# FXLoader_rev_A.net
KiCad netlist of a schematic drawn in EAGLE
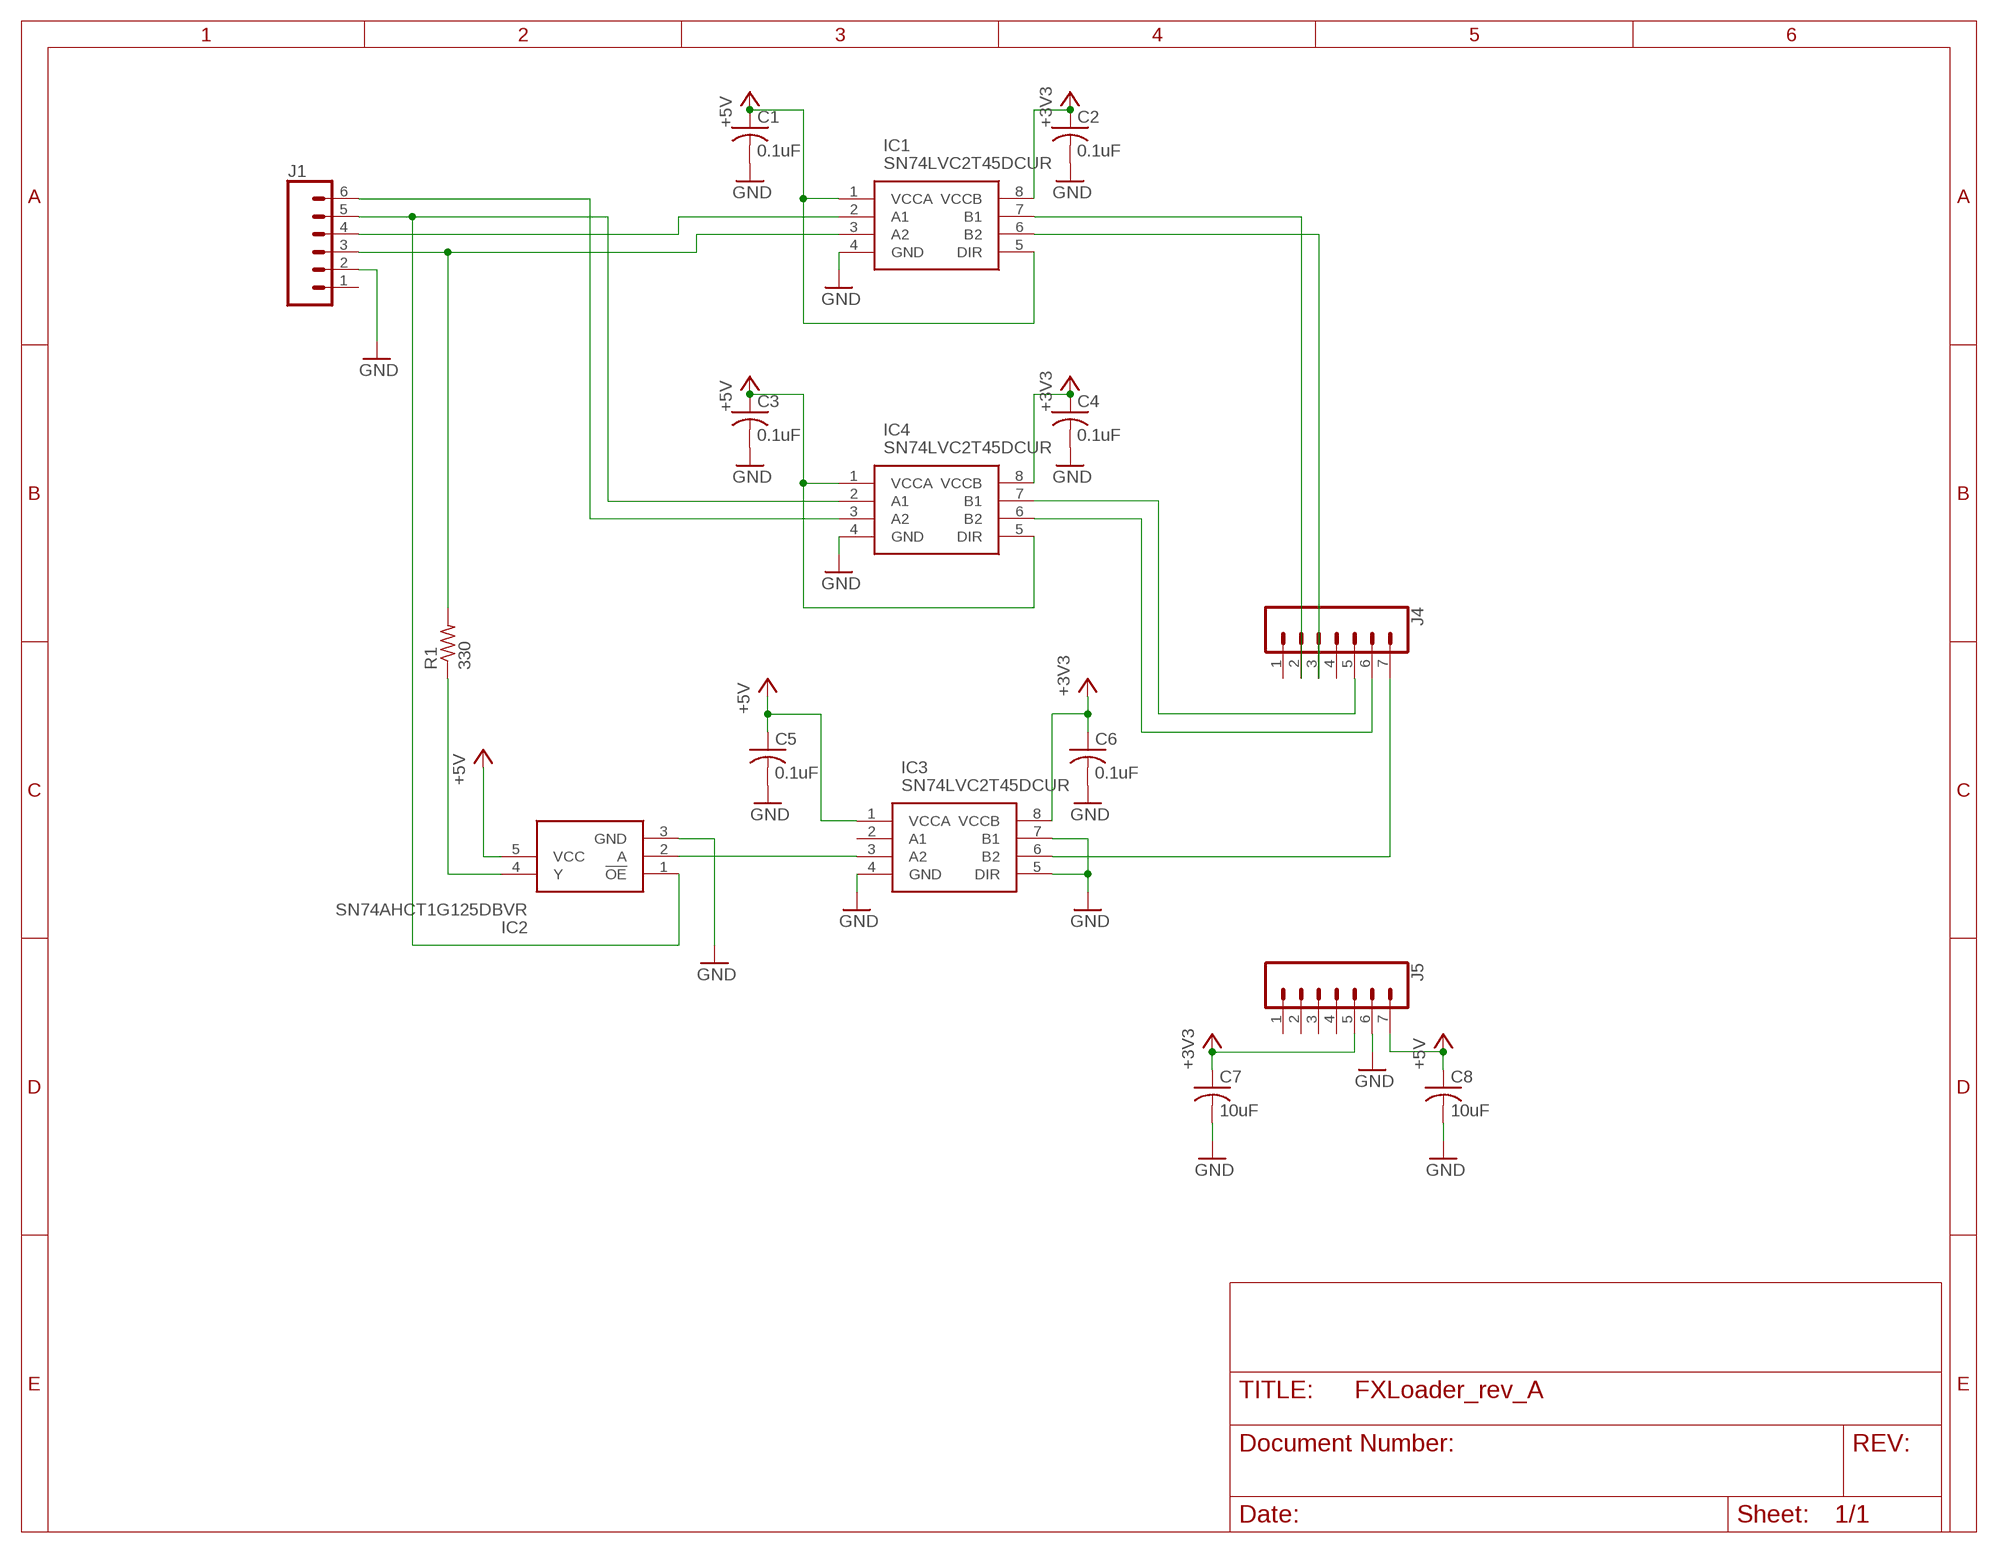
[diagram p0: schematic, sheet 1]

(export (version "E")
  (design (tool "Eeschema 10.0.6"))
  (components
    (comp (ref "C1")
      (value "0.1uF")
      (footprint "eagle-import:C0402")
      (libsource (lib "eagle-import") (part "C-USC0402"))
    )
    (comp (ref "C2")
      (value "0.1uF")
      (footprint "eagle-import:C0402")
      (libsource (lib "eagle-import") (part "C-USC0402"))
    )
    (comp (ref "C3")
      (value "0.1uF")
      (footprint "eagle-import:C0402")
      (libsource (lib "eagle-import") (part "C-USC0402"))
    )
    (comp (ref "C4")
      (value "0.1uF")
      (footprint "eagle-import:C0402")
      (libsource (lib "eagle-import") (part "C-USC0402"))
    )
    (comp (ref "C5")
      (value "0.1uF")
      (footprint "eagle-import:C0402")
      (libsource (lib "eagle-import") (part "C-USC0402"))
    )
    (comp (ref "C6")
      (value "0.1uF")
      (footprint "eagle-import:C0402")
      (libsource (lib "eagle-import") (part "C-USC0402"))
    )
    (comp (ref "C7")
      (value "10uF")
      (footprint "eagle-import:C0805")
      (libsource (lib "eagle-import") (part "C-USC0805"))
    )
    (comp (ref "C8")
      (value "10uF")
      (footprint "eagle-import:C0805")
      (libsource (lib "eagle-import") (part "C-USC0805"))
    )
    (comp (ref "IC1")
      (value "SN74LVC2T45DCUR")
      (footprint "eagle-import:SOP50P310X90-8N")
      (fields (field (name "MOUSER_PART_NUMBER") "595-SN74LVC2T45DCUR"))
      (libsource (lib "eagle-import") (part "SN74LVC2T45DCUR"))
    )
    (comp (ref "IC2")
      (value "SN74AHCT1G125DBVR")
      (footprint "eagle-import:SOT95P280X145-5N")
      (fields (field (name "MOUSER_PART_NUMBER") "595-SNAHCT1G125DBVR"))
      (libsource (lib "eagle-import") (part "SN74AHCT1G125DBVR"))
    )
    (comp (ref "IC3")
      (value "SN74LVC2T45DCUR")
      (footprint "eagle-import:SOP50P310X90-8N")
      (fields (field (name "MOUSER_PART_NUMBER") "595-SN74LVC2T45DCUR"))
      (libsource (lib "eagle-import") (part "SN74LVC2T45DCUR"))
    )
    (comp (ref "IC4")
      (value "SN74LVC2T45DCUR")
      (footprint "eagle-import:SOP50P310X90-8N")
      (fields (field (name "MOUSER_PART_NUMBER") "595-SN74LVC2T45DCUR"))
      (libsource (lib "eagle-import") (part "SN74LVC2T45DCUR"))
    )
    (comp (ref "J1")
      (value "CONN_06NO_SILK_FEMALE_PTH")
      (footprint "eagle-import:1X06_NO_SILK")
      (libsource (lib "eagle-import") (part "CONN_06NO_SILK_FEMALE_PTH"))
    )
    (comp (ref "J4")
      (value "CONN_071X07_LONGPADS_OFFSET_B")
      (footprint "eagle-import:1X07_LONGPADS_OFFSET_B")
      (libsource (lib "eagle-import") (part "CONN_071X07_LONGPADS_OFFSET_B"))
    )
    (comp (ref "J5")
      (value "CONN_071X07_LONGPADS_OFFSET")
      (footprint "eagle-import:1X07_LONGPADS_OFFSET")
      (libsource (lib "eagle-import") (part "CONN_071X07_LONGPADS_OFFSET"))
    )
    (comp (ref "R1")
      (value "330")
      (footprint "eagle-import:R0402")
      (libsource (lib "eagle-import") (part "R-US_R0402"))
    )
  )
  (nets
    (net (code "1") (name "+3V3") (class "Default")
      (node (ref "C2") (pin "1") (pinfunction "1_1") (pintype "passive"))
      (node (ref "C4") (pin "1") (pinfunction "1_1") (pintype "passive"))
      (node (ref "C6") (pin "1") (pinfunction "1_1") (pintype "passive"))
      (node (ref "C7") (pin "1") (pinfunction "1_1") (pintype "passive"))
      (node (ref "IC1") (pin "8") (pinfunction "VCCB_8") (pintype "bidirectional"))
      (node (ref "IC3") (pin "8") (pinfunction "VCCB_8") (pintype "bidirectional"))
      (node (ref "IC4") (pin "8") (pinfunction "VCCB_8") (pintype "bidirectional"))
      (node (ref "J5") (pin "5") (pinfunction "5_5") (pintype "passive"))
    )
    (net (code "2") (name "+5V") (class "Default")
      (node (ref "C1") (pin "1") (pinfunction "1_1") (pintype "passive"))
      (node (ref "C3") (pin "1") (pinfunction "1_1") (pintype "passive"))
      (node (ref "C5") (pin "1") (pinfunction "1_1") (pintype "passive"))
      (node (ref "C8") (pin "1") (pinfunction "1_1") (pintype "passive"))
      (node (ref "IC1") (pin "1") (pinfunction "VCCA_1") (pintype "bidirectional"))
      (node (ref "IC1") (pin "5") (pinfunction "DIR_5") (pintype "bidirectional"))
      (node (ref "IC2") (pin "5") (pinfunction "VCC_5") (pintype "power_in"))
      (node (ref "IC3") (pin "1") (pinfunction "VCCA_1") (pintype "bidirectional"))
      (node (ref "IC4") (pin "1") (pinfunction "VCCA_1") (pintype "bidirectional"))
      (node (ref "IC4") (pin "5") (pinfunction "DIR_5") (pintype "bidirectional"))
      (node (ref "J5") (pin "7") (pinfunction "7_7") (pintype "passive"))
    )
    (net (code "3") (name "GND") (class "Default")
      (node (ref "C1") (pin "2") (pinfunction "2_2") (pintype "passive"))
      (node (ref "C2") (pin "2") (pinfunction "2_2") (pintype "passive"))
      (node (ref "C3") (pin "2") (pinfunction "2_2") (pintype "passive"))
      (node (ref "C4") (pin "2") (pinfunction "2_2") (pintype "passive"))
      (node (ref "C5") (pin "2") (pinfunction "2_2") (pintype "passive"))
      (node (ref "C6") (pin "2") (pinfunction "2_2") (pintype "passive"))
      (node (ref "C7") (pin "2") (pinfunction "2_2") (pintype "passive"))
      (node (ref "C8") (pin "2") (pinfunction "2_2") (pintype "passive"))
      (node (ref "IC1") (pin "4") (pinfunction "GND_4") (pintype "bidirectional"))
      (node (ref "IC2") (pin "3") (pinfunction "GND_3") (pintype "power_in"))
      (node (ref "IC3") (pin "4") (pinfunction "GND_4") (pintype "bidirectional"))
      (node (ref "IC3") (pin "5") (pinfunction "DIR_5") (pintype "bidirectional"))
      (node (ref "IC3") (pin "7") (pinfunction "B1_7") (pintype "bidirectional"))
      (node (ref "IC4") (pin "4") (pinfunction "GND_4") (pintype "bidirectional"))
      (node (ref "J1") (pin "2") (pinfunction "2_2") (pintype "passive"))
      (node (ref "J5") (pin "6") (pinfunction "6_6") (pintype "passive"))
    )
    (net (code "4") (name "Net-(IC1-A1)") (class "Default")
      (node (ref "IC1") (pin "2") (pinfunction "A1_2") (pintype "bidirectional"))
      (node (ref "J1") (pin "4") (pinfunction "4_4") (pintype "passive"))
    )
    (net (code "5") (name "Net-(IC1-A2)") (class "Default")
      (node (ref "IC1") (pin "3") (pinfunction "A2_3") (pintype "bidirectional"))
      (node (ref "J1") (pin "3") (pinfunction "3_3") (pintype "passive"))
      (node (ref "R1") (pin "2") (pinfunction "2_2") (pintype "passive"))
    )
    (net (code "6") (name "Net-(IC1-B1)") (class "Default")
      (node (ref "IC1") (pin "7") (pinfunction "B1_7") (pintype "bidirectional"))
      (node (ref "J4") (pin "2") (pinfunction "2_2") (pintype "passive"))
    )
    (net (code "7") (name "Net-(IC1-B2)") (class "Default")
      (node (ref "IC1") (pin "6") (pinfunction "B2_6") (pintype "bidirectional"))
      (node (ref "J4") (pin "3") (pinfunction "3_3") (pintype "passive"))
    )
    (net (code "8") (name "Net-(IC2-A)") (class "Default")
      (node (ref "IC2") (pin "2") (pinfunction "A_2") (pintype "bidirectional"))
      (node (ref "IC3") (pin "3") (pinfunction "A2_3") (pintype "bidirectional"))
    )
    (net (code "9") (name "Net-(IC2-Y)") (class "Default")
      (node (ref "IC2") (pin "4") (pinfunction "Y_4") (pintype "bidirectional"))
      (node (ref "R1") (pin "1") (pinfunction "1_1") (pintype "passive"))
    )
    (net (code "10") (name "Net-(IC2-~{OE})") (class "Default")
      (node (ref "IC2") (pin "1") (pinfunction "~{OE}_1") (pintype "bidirectional"))
      (node (ref "IC4") (pin "2") (pinfunction "A1_2") (pintype "bidirectional"))
      (node (ref "J1") (pin "5") (pinfunction "5_5") (pintype "passive"))
    )
    (net (code "11") (name "Net-(IC3-B2)") (class "Default")
      (node (ref "IC3") (pin "6") (pinfunction "B2_6") (pintype "bidirectional"))
      (node (ref "J4") (pin "7") (pinfunction "7_7") (pintype "passive"))
    )
    (net (code "12") (name "Net-(IC4-A2)") (class "Default")
      (node (ref "IC4") (pin "3") (pinfunction "A2_3") (pintype "bidirectional"))
      (node (ref "J1") (pin "6") (pinfunction "6_6") (pintype "passive"))
    )
    (net (code "13") (name "Net-(IC4-B1)") (class "Default")
      (node (ref "IC4") (pin "7") (pinfunction "B1_7") (pintype "bidirectional"))
      (node (ref "J4") (pin "5") (pinfunction "5_5") (pintype "passive"))
    )
    (net (code "14") (name "Net-(IC4-B2)") (class "Default")
      (node (ref "IC4") (pin "6") (pinfunction "B2_6") (pintype "bidirectional"))
      (node (ref "J4") (pin "6") (pinfunction "6_6") (pintype "passive"))
    )
    (net (code "15") (name "unconnected-(IC3-A1-Pad2)") (class "Default")
      (node (ref "IC3") (pin "2") (pinfunction "A1_2") (pintype "bidirectional"))
    )
    (net (code "16") (name "unconnected-(J1-Pad1)") (class "Default")
      (node (ref "J1") (pin "1") (pinfunction "1_1") (pintype "passive"))
    )
    (net (code "17") (name "unconnected-(J4-Pad1)") (class "Default")
      (node (ref "J4") (pin "1") (pinfunction "1_1") (pintype "passive"))
    )
    (net (code "18") (name "unconnected-(J4-Pad4)") (class "Default")
      (node (ref "J4") (pin "4") (pinfunction "4_4") (pintype "passive"))
    )
    (net (code "19") (name "unconnected-(J5-Pad1)") (class "Default")
      (node (ref "J5") (pin "1") (pinfunction "1_1") (pintype "passive"))
    )
    (net (code "20") (name "unconnected-(J5-Pad2)") (class "Default")
      (node (ref "J5") (pin "2") (pinfunction "2_2") (pintype "passive"))
    )
    (net (code "21") (name "unconnected-(J5-Pad3)") (class "Default")
      (node (ref "J5") (pin "3") (pinfunction "3_3") (pintype "passive"))
    )
    (net (code "22") (name "unconnected-(J5-Pad4)") (class "Default")
      (node (ref "J5") (pin "4") (pinfunction "4_4") (pintype "passive"))
    )
  )
)
